# ETH.net
KiCad netlist of a schematic drawn in Altium Designer
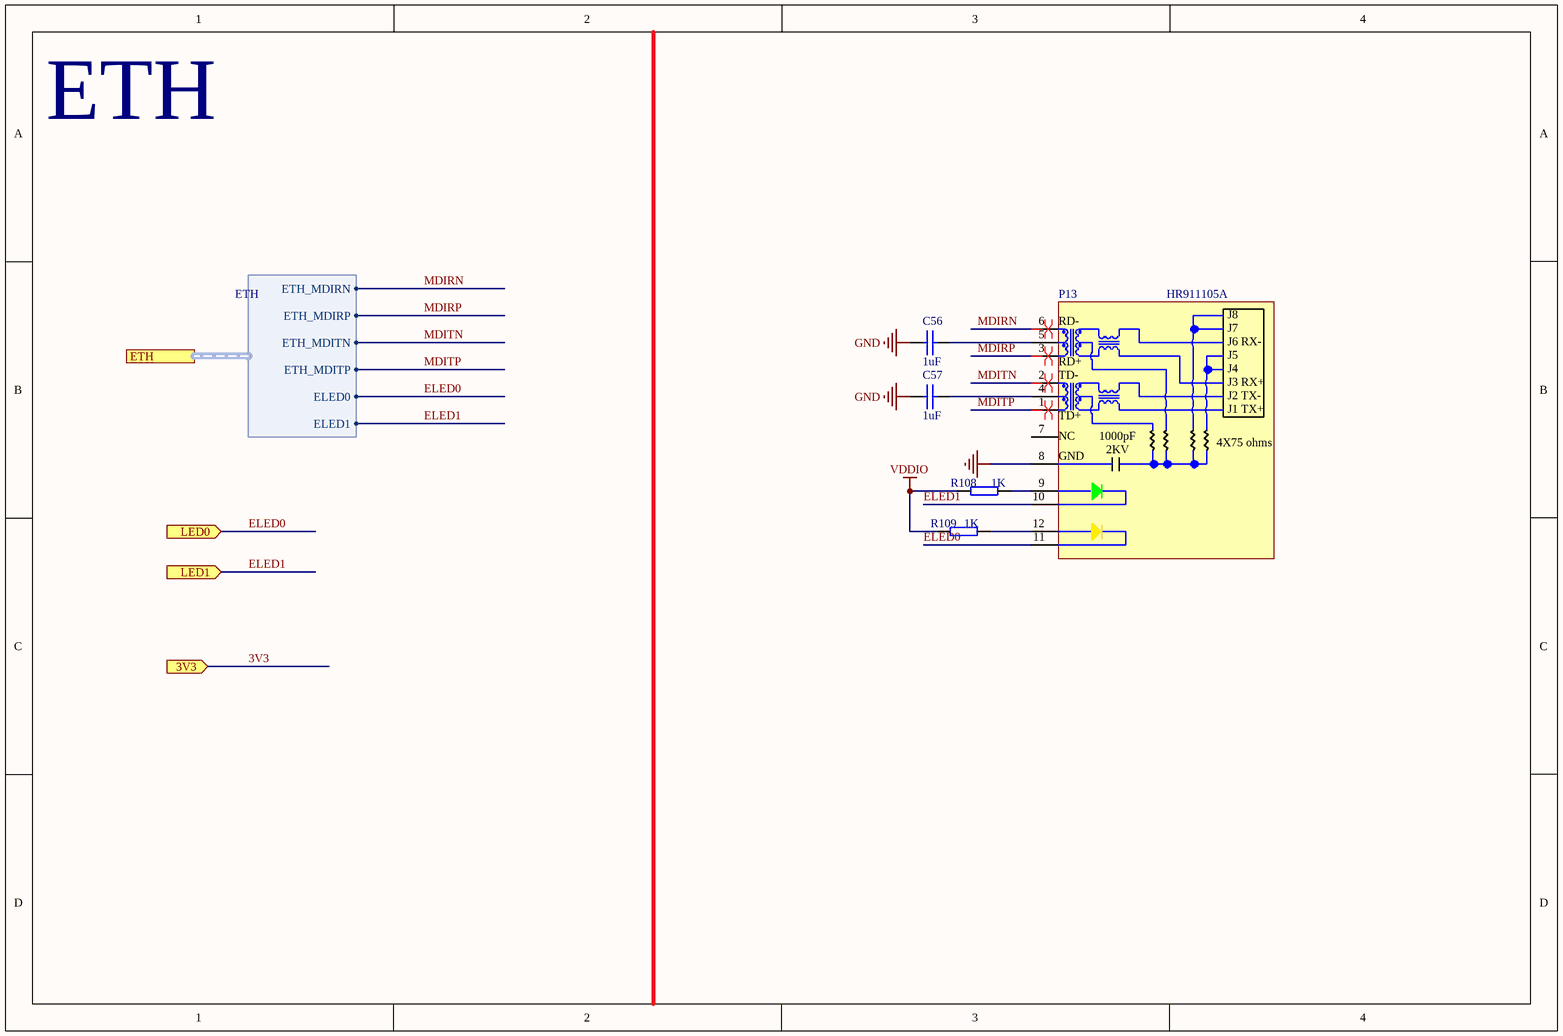
[diagram p0: ETH.SchDoc]

(export (version "E")
  (design (tool "Eeschema 10.0.6"))
  (components
    (comp (ref "C56")
      (value "1uF")
      (footprint "0402_C")
      (description "Capacitor")
      (libsource (lib "wch_sch_others") (part "CAP"))
    )
    (comp (ref "C57")
      (value "1uF")
      (footprint "0402_C")
      (description "Capacitor")
      (libsource (lib "wch_sch_others") (part "CAP"))
    )
    (comp (ref "P13") (value "HR911105A") (footprint "HR911105A") (libsource (lib "*") (part "HR911105A")))
    (comp (ref "R108") (value "1K") (footprint "0402") (libsource (lib "wch_sch_others") (part "RES")))
    (comp (ref "R109") (value "1K") (footprint "0402") (libsource (lib "wch_sch_others") (part "RES")))
  )
  (nets
    (net (code "3") (name "/ELED0") (class "Default") (node (ref "P13") (pin "11") (pintype "passive")))
    (net (code "4") (name "/ELED1") (class "Default") (node (ref "P13") (pin "10") (pintype "passive")))
    (net (code "5") (name "/MDIRN") (class "Default") (node (ref "P13") (pin "6") (pintype "passive")))
    (net (code "6") (name "/MDIRP") (class "Default") (node (ref "P13") (pin "3") (pintype "passive")))
    (net (code "7") (name "/MDITN") (class "Default") (node (ref "P13") (pin "2") (pintype "passive")))
    (net (code "8") (name "/MDITP") (class "Default") (node (ref "P13") (pin "1") (pintype "passive")))
    (net (code "10") (name "GND") (class "Default")
      (node (ref "C56") (pin "1") (pinfunction "1_1") (pintype "passive"))
      (node (ref "C57") (pin "1") (pinfunction "1_1") (pintype "passive"))
      (node (ref "P13") (pin "8") (pintype "passive"))
    )
    (net (code "11") (name "Net-(C56-Pad2)") (class "Default")
      (node (ref "C56") (pin "2") (pinfunction "2_2") (pintype "passive"))
      (node (ref "P13") (pin "5") (pintype "passive"))
    )
    (net (code "12") (name "Net-(C57-Pad2)") (class "Default")
      (node (ref "C57") (pin "2") (pinfunction "2_2") (pintype "passive"))
      (node (ref "P13") (pin "4") (pintype "passive"))
    )
    (net (code "13") (name "Net-(P13-Pad9)") (class "Default")
      (node (ref "P13") (pin "9") (pintype "passive"))
      (node (ref "R108") (pin "2") (pintype "passive"))
    )
    (net (code "14") (name "Net-(P13-Pad12)") (class "Default")
      (node (ref "P13") (pin "12") (pintype "passive"))
      (node (ref "R109") (pin "2") (pintype "passive"))
    )
    (net (code "15") (name "VDDIO") (class "Default")
      (node (ref "R108") (pin "1") (pintype "passive"))
      (node (ref "R109") (pin "1") (pintype "passive"))
    )
    (net (code "16") (name "unconnected-(P13-Pad7)") (class "Default")
      (node (ref "P13") (pin "7") (pintype "passive"))
    )
  )
)
